# feather_wing.net
KiCad netlist of a schematic drawn in EAGLE
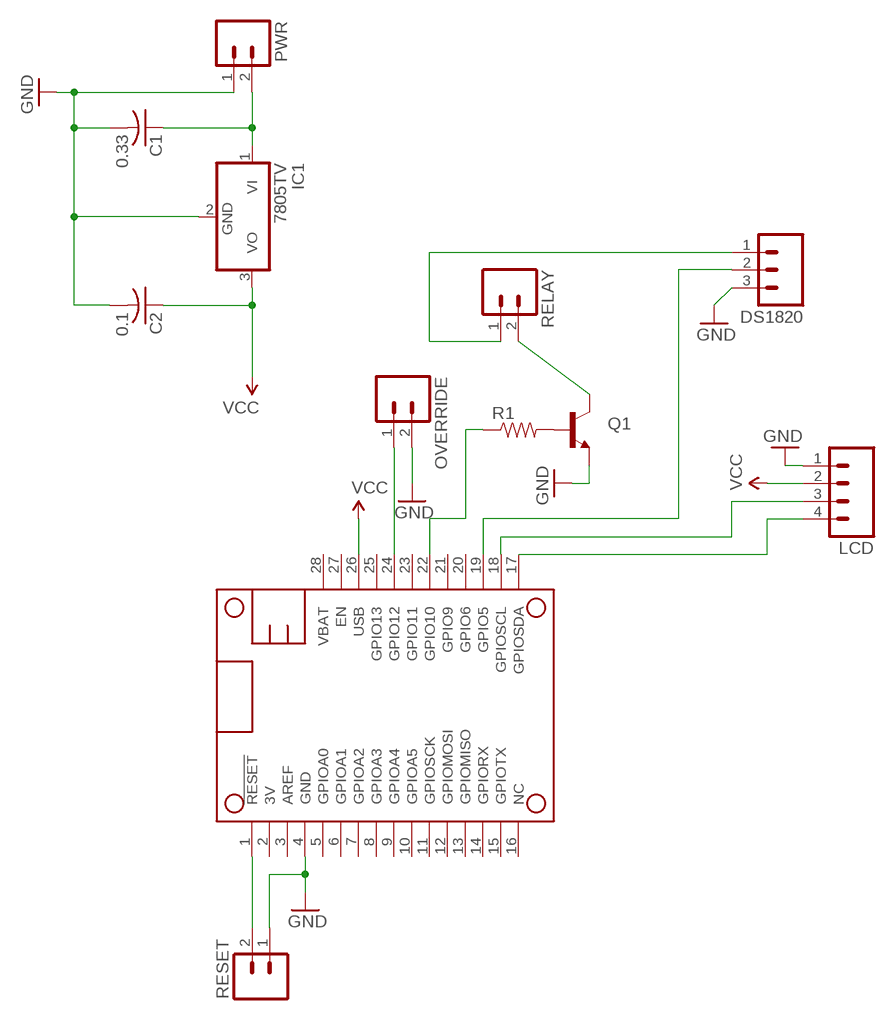
[diagram p0: schematic, sheet 1]

(export (version "E")
  (design (tool "Eeschema 10.0.6"))
  (components
    (comp (ref "C1")
      (value "0.33")
      (footprint "eagle-import:C025-025X050")
      (libsource (lib "eagle-import") (part "C-US025-025X050"))
    )
    (comp (ref "C2")
      (value "0.1")
      (footprint "eagle-import:C025-025X050")
      (libsource (lib "eagle-import") (part "C-US025-025X050"))
    )
    (comp (ref "DS1820")
      (value "M03SCREW")
      (footprint "eagle-import:SCREWTERMINAL-3.5MM-3")
      (libsource (lib "eagle-import") (part "M03SCREW"))
    )
    (comp (ref "IC1")
      (value "7805TV")
      (footprint "eagle-import:TO220V")
      (libsource (lib "eagle-import") (part "78TV05"))
    )
    (comp (ref "LCD")
      (value "M04LOCK")
      (footprint "eagle-import:1X04_LOCK")
      (libsource (lib "eagle-import") (part "M04LOCK"))
    )
    (comp (ref "MS1")
      (value "FEATHERWING")
      (footprint "eagle-import:FEATHERWING")
      (libsource (lib "eagle-import") (part "FEATHERWING"))
    )
    (comp (ref "OVERRIDE")
      (value "M02PTH")
      (footprint "eagle-import:1X02")
      (libsource (lib "eagle-import") (part "M02PTH"))
    )
    (comp (ref "PWR")
      (value "M023.5MM")
      (footprint "eagle-import:SCREWTERMINAL-3.5MM-2")
      (libsource (lib "eagle-import") (part "M023.5MM"))
    )
    (comp (ref "Q1")
      (value "TRANSISTOR_NPNP2N2222A")
      (footprint "eagle-import:TO-92")
      (libsource (lib "eagle-import") (part "TRANSISTOR_NPNP2N2222A"))
    )
    (comp (ref "R1")
      (value "RESISTORAXIAL-0.3")
      (footprint "eagle-import:AXIAL-0.3")
      (libsource (lib "eagle-import") (part "RESISTORAXIAL-0.3"))
    )
    (comp (ref "RELAY")
      (value "M023.5MM")
      (footprint "eagle-import:SCREWTERMINAL-3.5MM-2")
      (libsource (lib "eagle-import") (part "M023.5MM"))
    )
    (comp (ref "RESET")
      (value "M02PTH")
      (footprint "eagle-import:1X02")
      (libsource (lib "eagle-import") (part "M02PTH"))
    )
  )
  (nets
    (net (code "1") (name "/3V") (class "Default")
      (node (ref "MS1") (pin "2") (pinfunction "3V_2") (pintype "power_in"))
    )
    (net (code "2") (name "/VBAT") (class "Default")
      (node (ref "MS1") (pin "28") (pinfunction "VBAT_28") (pintype "power_in"))
    )
    (net (code "3") (name "GND") (class "Default")
      (node (ref "C1") (pin "2") (pinfunction "2_2") (pintype "passive"))
      (node (ref "C2") (pin "2") (pinfunction "2_2") (pintype "passive"))
      (node (ref "DS1820") (pin "3") (pinfunction "3_3") (pintype "passive"))
      (node (ref "IC1") (pin "2") (pinfunction "GND_2") (pintype "passive"))
      (node (ref "LCD") (pin "1") (pinfunction "1_1") (pintype "passive"))
      (node (ref "MS1") (pin "4") (pinfunction "GND_4") (pintype "power_in"))
      (node (ref "OVERRIDE") (pin "2") (pinfunction "2_2") (pintype "passive"))
      (node (ref "PWR") (pin "1") (pinfunction "1_1") (pintype "passive"))
      (node (ref "Q1") (pin "3") (pinfunction "E_3") (pintype "passive"))
      (node (ref "RESET") (pin "1") (pinfunction "1_1") (pintype "passive"))
    )
    (net (code "4") (name "Net-(DS1820-Pad1)") (class "Default")
      (node (ref "DS1820") (pin "1") (pinfunction "1_1") (pintype "passive"))
      (node (ref "RELAY") (pin "1") (pinfunction "1_1") (pintype "passive"))
    )
    (net (code "5") (name "Net-(IC1-VI)") (class "Default")
      (node (ref "C1") (pin "1") (pinfunction "1_1") (pintype "passive"))
      (node (ref "IC1") (pin "1") (pinfunction "VI_1") (pintype "input"))
      (node (ref "PWR") (pin "2") (pinfunction "2_2") (pintype "passive"))
    )
    (net (code "6") (name "Net-(MS1-GPIO5)") (class "Default")
      (node (ref "DS1820") (pin "2") (pinfunction "2_2") (pintype "passive"))
      (node (ref "MS1") (pin "19") (pinfunction "GPIO5_19") (pintype "bidirectional"))
    )
    (net (code "7") (name "Net-(MS1-GPIO10)") (class "Default")
      (node (ref "MS1") (pin "22") (pinfunction "GPIO10_22") (pintype "bidirectional"))
      (node (ref "R1") (pin "P$1") (pinfunction "1_P$1") (pintype "passive"))
    )
    (net (code "8") (name "Net-(MS1-GPIO12)") (class "Default")
      (node (ref "MS1") (pin "24") (pinfunction "GPIO12_24") (pintype "bidirectional"))
      (node (ref "OVERRIDE") (pin "1") (pinfunction "1_1") (pintype "passive"))
    )
    (net (code "9") (name "Net-(MS1-GPIOSCL)") (class "Default")
      (node (ref "LCD") (pin "3") (pinfunction "3_3") (pintype "passive"))
      (node (ref "MS1") (pin "18") (pinfunction "GPIOSCL_18") (pintype "bidirectional"))
    )
    (net (code "10") (name "Net-(MS1-GPIOSDA)") (class "Default")
      (node (ref "LCD") (pin "4") (pinfunction "4_4") (pintype "passive"))
      (node (ref "MS1") (pin "17") (pinfunction "GPIOSDA_17") (pintype "bidirectional"))
    )
    (net (code "11") (name "Net-(MS1-~{RESET})") (class "Default")
      (node (ref "MS1") (pin "1") (pinfunction "~{RESET}_1") (pintype "input"))
      (node (ref "RESET") (pin "2") (pinfunction "2_2") (pintype "passive"))
    )
    (net (code "12") (name "Net-(Q1-B)") (class "Default")
      (node (ref "Q1") (pin "2") (pinfunction "B_2") (pintype "passive"))
      (node (ref "R1") (pin "P$2") (pinfunction "2_P$2") (pintype "passive"))
    )
    (net (code "13") (name "Net-(Q1-C)") (class "Default")
      (node (ref "Q1") (pin "1") (pinfunction "C_1") (pintype "passive"))
      (node (ref "RELAY") (pin "2") (pinfunction "2_2") (pintype "passive"))
    )
    (net (code "14") (name "VCC") (class "Default")
      (node (ref "C2") (pin "1") (pinfunction "1_1") (pintype "passive"))
      (node (ref "IC1") (pin "3") (pinfunction "VO_3") (pintype "passive"))
      (node (ref "LCD") (pin "2") (pinfunction "2_2") (pintype "passive"))
      (node (ref "MS1") (pin "26") (pinfunction "USB_26") (pintype "power_in"))
    )
    (net (code "15") (name "unconnected-(MS1-AREF-Pad3)") (class "Default")
      (node (ref "MS1") (pin "3") (pinfunction "AREF_3") (pintype "passive"))
    )
    (net (code "16") (name "unconnected-(MS1-EN-Pad27)") (class "Default")
      (node (ref "MS1") (pin "27") (pinfunction "EN_27") (pintype "passive"))
    )
    (net (code "17") (name "unconnected-(MS1-GPIO6-Pad20)") (class "Default")
      (node (ref "MS1") (pin "20") (pinfunction "GPIO6_20") (pintype "bidirectional"))
    )
    (net (code "18") (name "unconnected-(MS1-GPIO9-Pad21)") (class "Default")
      (node (ref "MS1") (pin "21") (pinfunction "GPIO9_21") (pintype "bidirectional"))
    )
    (net (code "19") (name "unconnected-(MS1-GPIO11-Pad23)") (class "Default")
      (node (ref "MS1") (pin "23") (pinfunction "GPIO11_23") (pintype "bidirectional"))
    )
    (net (code "20") (name "unconnected-(MS1-GPIO13-Pad25)") (class "Default")
      (node (ref "MS1") (pin "25") (pinfunction "GPIO13_25") (pintype "bidirectional"))
    )
    (net (code "21") (name "unconnected-(MS1-GPIOA0-Pad5)") (class "Default")
      (node (ref "MS1") (pin "5") (pinfunction "GPIOA0_5") (pintype "bidirectional"))
    )
    (net (code "22") (name "unconnected-(MS1-GPIOA1-Pad6)") (class "Default")
      (node (ref "MS1") (pin "6") (pinfunction "GPIOA1_6") (pintype "bidirectional"))
    )
    (net (code "23") (name "unconnected-(MS1-GPIOA2-Pad7)") (class "Default")
      (node (ref "MS1") (pin "7") (pinfunction "GPIOA2_7") (pintype "bidirectional"))
    )
    (net (code "24") (name "unconnected-(MS1-GPIOA3-Pad8)") (class "Default")
      (node (ref "MS1") (pin "8") (pinfunction "GPIOA3_8") (pintype "bidirectional"))
    )
    (net (code "25") (name "unconnected-(MS1-GPIOA4-Pad9)") (class "Default")
      (node (ref "MS1") (pin "9") (pinfunction "GPIOA4_9") (pintype "bidirectional"))
    )
    (net (code "26") (name "unconnected-(MS1-GPIOA5-Pad10)") (class "Default")
      (node (ref "MS1") (pin "10") (pinfunction "GPIOA5_10") (pintype "bidirectional"))
    )
    (net (code "27") (name "unconnected-(MS1-GPIOMISO-Pad13)") (class "Default")
      (node (ref "MS1") (pin "13") (pinfunction "GPIOMISO_13") (pintype "bidirectional"))
    )
    (net (code "28") (name "unconnected-(MS1-GPIOMOSI-Pad12)") (class "Default")
      (node (ref "MS1") (pin "12") (pinfunction "GPIOMOSI_12") (pintype "bidirectional"))
    )
    (net (code "29") (name "unconnected-(MS1-GPIORX-Pad14)") (class "Default")
      (node (ref "MS1") (pin "14") (pinfunction "GPIORX_14") (pintype "bidirectional"))
    )
    (net (code "30") (name "unconnected-(MS1-GPIOSCK-Pad11)") (class "Default")
      (node (ref "MS1") (pin "11") (pinfunction "GPIOSCK_11") (pintype "bidirectional"))
    )
    (net (code "31") (name "unconnected-(MS1-GPIOTX-Pad15)") (class "Default")
      (node (ref "MS1") (pin "15") (pinfunction "GPIOTX_15") (pintype "bidirectional"))
    )
    (net (code "32") (name "unconnected-(MS1-NC-Pad16)") (class "Default")
      (node (ref "MS1") (pin "16") (pinfunction "NC_16") (pintype "passive"))
    )
  )
)
